# STM32F1_720.net
KiCad netlist of a schematic drawn in Altium Designer
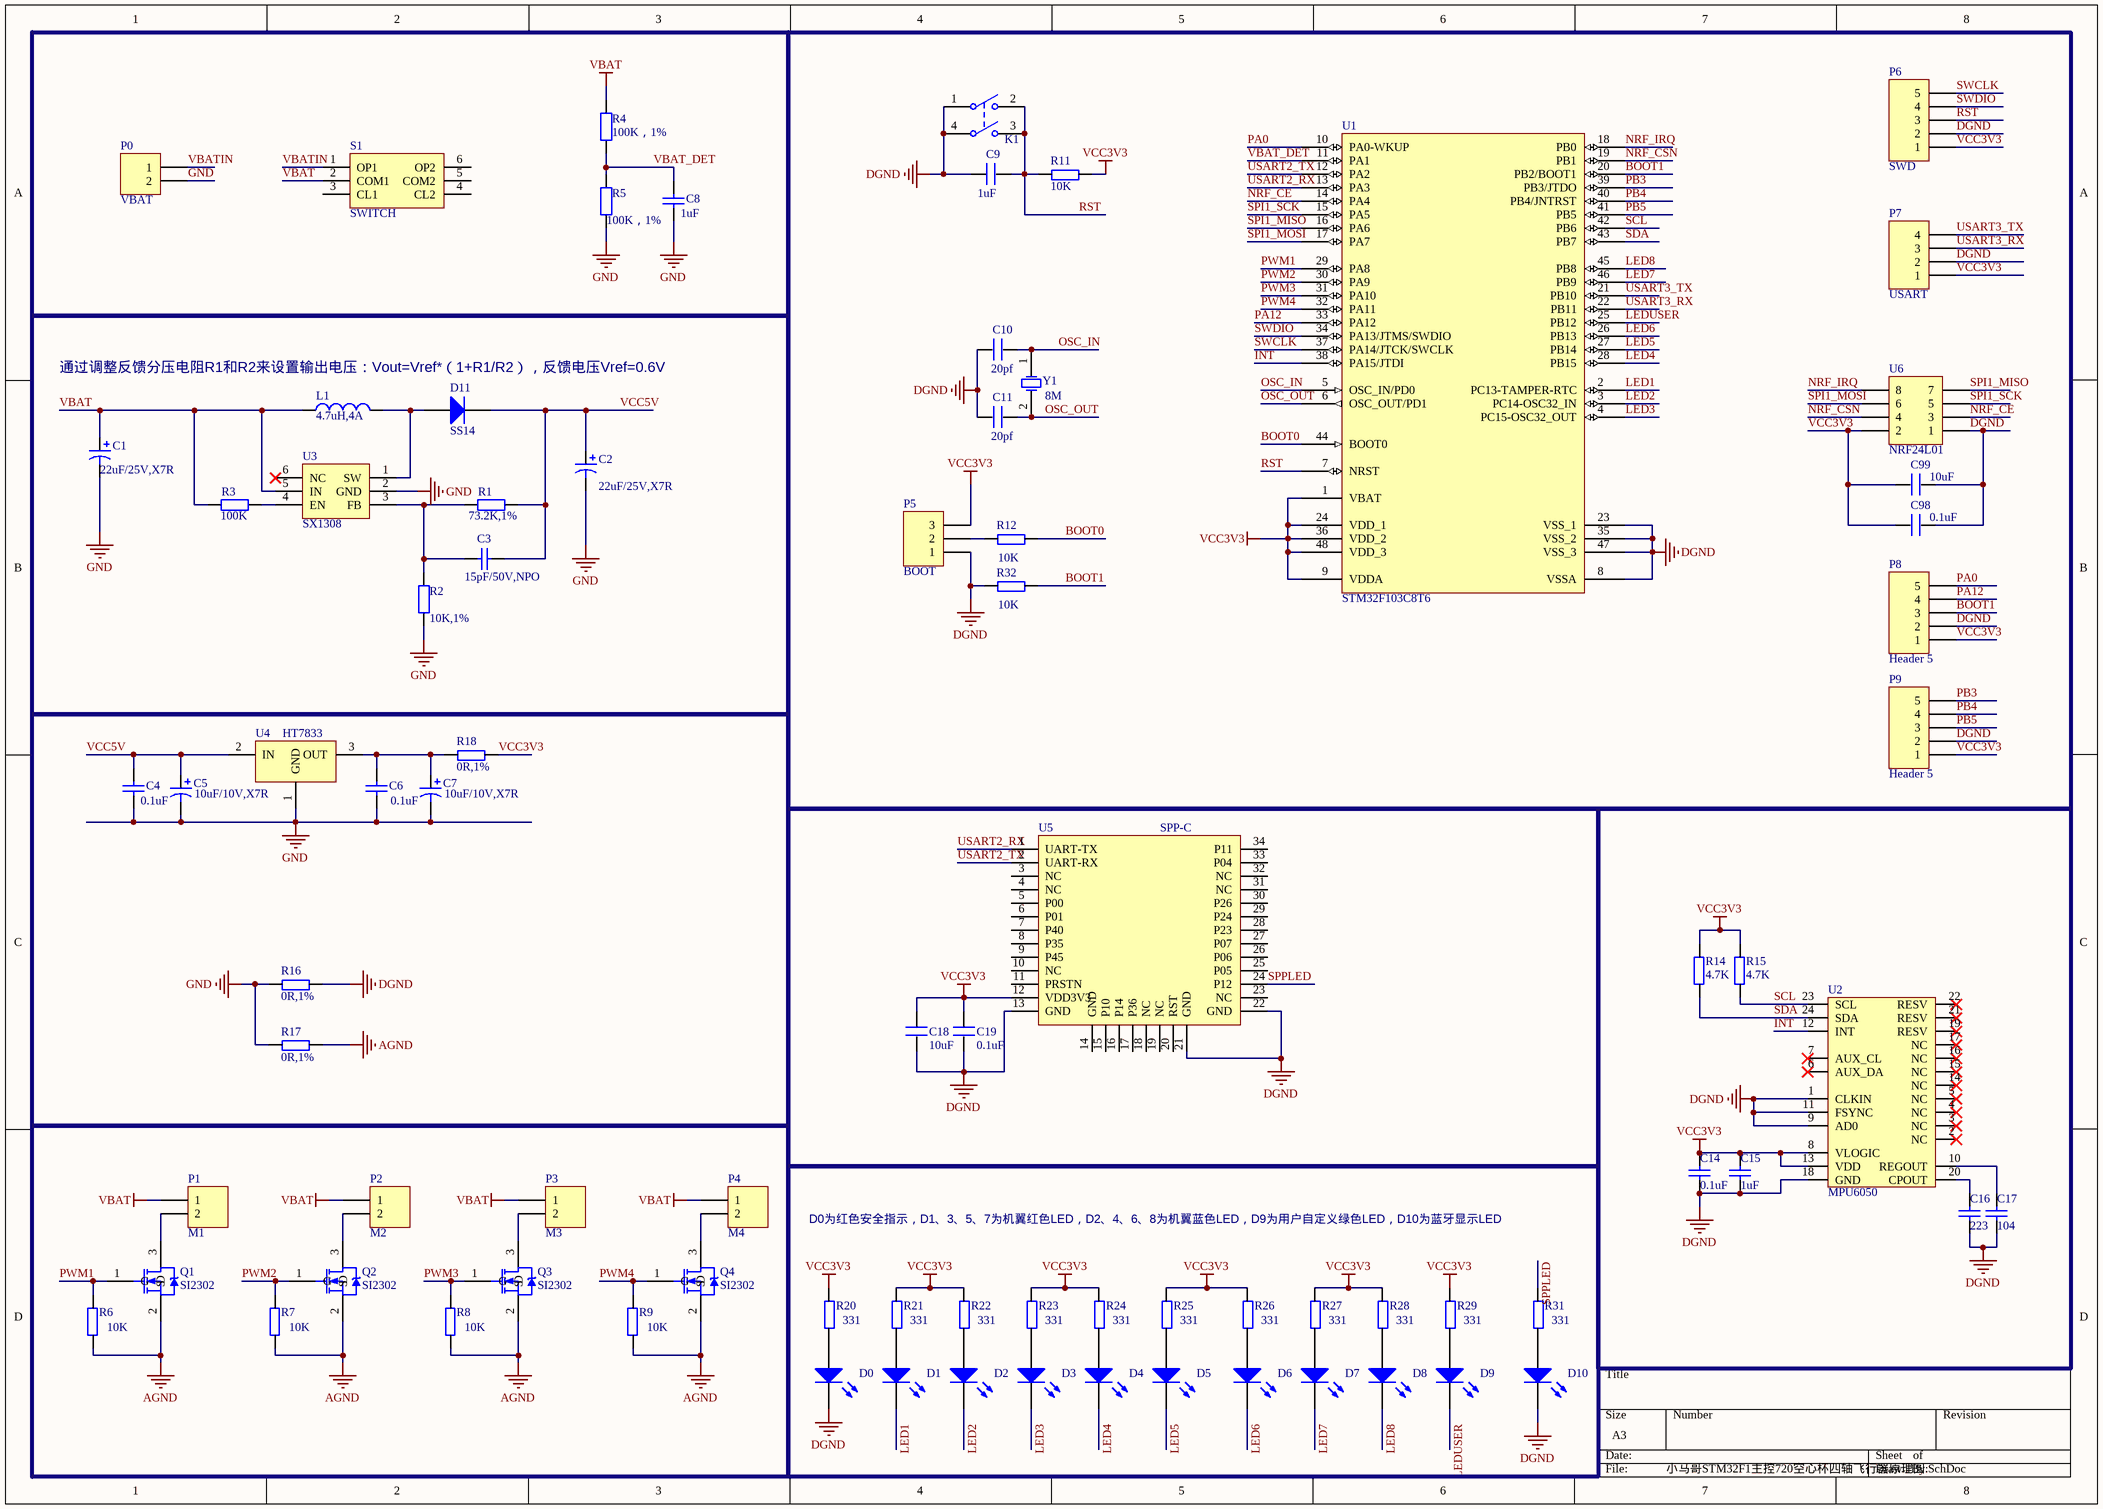
[diagram p0: 小马哥STM32F1主控720空心杯四轴飞行器原理图.SchDoc]

(export (version "E")
  (design (tool "Eeschema 10.0.6"))
  (components
    (comp (ref "C1")
      (value "22uF/25V,X7R")
      (footprint "LC-1206_C")
      (description "Polarized Capacitor (Radial)")
      (fields (field (name "Comment") "Cap Pol1") (field (name "PUBLISHER") "Altium Limited"))
      (libsource (lib "Miscellaneous Devices") (part "Cap Pol1"))
    )
    (comp (ref "C2")
      (value "22uF/25V,X7R")
      (footprint "LC-1206_C")
      (description "Polarized Capacitor (Radial)")
      (fields (field (name "Comment") "Cap Pol1") (field (name "PUBLISHER") "Altium Limited"))
      (libsource (lib "Miscellaneous Devices") (part "Cap Pol1"))
    )
    (comp (ref "C3")
      (value "15pF/50V,NPO")
      (footprint "LC-0603_C")
      (description "Capacitor")
      (fields (field (name "Comment") "Cap") (field (name "PUBLISHER") "Altium Limited"))
      (libsource (lib "Miscellaneous Devices") (part "Cap"))
    )
    (comp (ref "C4")
      (value "0.1uF")
      (footprint "LC-0603_C")
      (description "Capacitor")
      (fields (field (name "Comment") "Cap") (field (name "PUBLISHER") "Altium Limited"))
      (libsource (lib "Miscellaneous Devices") (part "Cap"))
    )
    (comp (ref "C5")
      (value "10uF/10V,X7R")
      (footprint "LC-1206_C")
      (description "Polarized Capacitor (Radial)")
      (fields (field (name "Comment") "Cap Pol1") (field (name "PUBLISHER") "Altium Limited"))
      (libsource (lib "Miscellaneous Devices") (part "Cap Pol1"))
    )
    (comp (ref "C6")
      (value "0.1uF")
      (footprint "LC-0603_C")
      (description "Capacitor")
      (fields (field (name "Comment") "Cap") (field (name "PUBLISHER") "Altium Limited"))
      (libsource (lib "Miscellaneous Devices") (part "Cap"))
    )
    (comp (ref "C7")
      (value "10uF/10V,X7R")
      (footprint "LC-1206_C")
      (description "Polarized Capacitor (Radial)")
      (fields (field (name "Comment") "Cap Pol1") (field (name "PUBLISHER") "Altium Limited"))
      (libsource (lib "Miscellaneous Devices") (part "Cap Pol1"))
    )
    (comp (ref "C8")
      (value "1uF")
      (footprint "LC-0603_C")
      (description "Capacitor")
      (fields (field (name "Comment") "Cap") (field (name "PUBLISHER") "Altium Limited"))
      (libsource (lib "Miscellaneous Devices") (part "Cap"))
    )
    (comp (ref "C9")
      (value "1uF")
      (footprint "LC-0603_C")
      (libsource (lib "Explorer STM32F407封装库") (part "C_1"))
    )
    (comp (ref "C10")
      (value "20pf")
      (footprint "LC-0603_C")
      (libsource (lib "Explorer STM32F407封装库") (part "C"))
    )
    (comp (ref "C11")
      (value "20pf")
      (footprint "LC-0603_C")
      (libsource (lib "Explorer STM32F407封装库") (part "C"))
    )
    (comp (ref "C14")
      (value "0.1uF")
      (footprint "LC-0603_C")
      (description "Capacitor")
      (fields (field (name "PUBLISHER") "Altium Limited"))
      (libsource (lib "Miscellaneous Devices") (part "Cap"))
    )
    (comp (ref "C15")
      (value "1uF")
      (footprint "LC-0603_C")
      (description "Capacitor")
      (fields (field (name "PUBLISHER") "Altium Limited"))
      (libsource (lib "Miscellaneous Devices") (part "Cap"))
    )
    (comp (ref "C16")
      (value "223")
      (footprint "LC-0603_C")
      (description "Capacitor")
      (fields (field (name "PUBLISHER") "Altium Limited"))
      (libsource (lib "Miscellaneous Devices") (part "Cap"))
    )
    (comp (ref "C17")
      (value "104")
      (footprint "LC-0603_C")
      (description "Capacitor")
      (fields (field (name "PUBLISHER") "Altium Limited"))
      (libsource (lib "Miscellaneous Devices") (part "Cap"))
    )
    (comp (ref "C18")
      (value "10uF")
      (footprint "LC-0805_C")
      (libsource (lib "Explorer STM32F407封装库") (part "C"))
    )
    (comp (ref "C19")
      (value "0.1uF")
      (footprint "LC-0603_C")
      (libsource (lib "Explorer STM32F407封装库") (part "C"))
    )
    (comp (ref "C98")
      (value "0.1uF")
      (footprint "LC-0603_C")
      (fields (field (name "Comment") "1uF"))
      (libsource (lib "Explorer STM32F407封装库") (part "C_1"))
    )
    (comp (ref "C99")
      (value "10uF")
      (footprint "LC-0805_C")
      (fields (field (name "Comment") "1uF"))
      (libsource (lib "Explorer STM32F407封装库") (part "C_1"))
    )
    (comp (ref "D0")
      (value "LED0")
      (footprint "LC-0805_LED_S1")
      (description "Typical INFRARED GaAs LED")
      (fields (field (name "PUBLISHER") "Altium Limited"))
      (libsource (lib "Miscellaneous Devices") (part "LED0"))
    )
    (comp (ref "D1")
      (value "LED0")
      (footprint "LC-0805_LED_S1")
      (description "Typical INFRARED GaAs LED")
      (fields (field (name "PUBLISHER") "Altium Limited"))
      (libsource (lib "Miscellaneous Devices") (part "LED0"))
    )
    (comp (ref "D2")
      (value "LED0")
      (footprint "LC-0805_LED_S1")
      (description "Typical INFRARED GaAs LED")
      (fields (field (name "PUBLISHER") "Altium Limited"))
      (libsource (lib "Miscellaneous Devices") (part "LED0"))
    )
    (comp (ref "D3")
      (value "LED0")
      (footprint "LC-0805_LED_S1")
      (description "Typical INFRARED GaAs LED")
      (fields (field (name "PUBLISHER") "Altium Limited"))
      (libsource (lib "Miscellaneous Devices") (part "LED0"))
    )
    (comp (ref "D4")
      (value "LED0")
      (footprint "LC-0805_LED_S1")
      (description "Typical INFRARED GaAs LED")
      (fields (field (name "PUBLISHER") "Altium Limited"))
      (libsource (lib "Miscellaneous Devices") (part "LED0"))
    )
    (comp (ref "D5")
      (value "LED0")
      (footprint "LC-0805_LED_S1")
      (description "Typical INFRARED GaAs LED")
      (fields (field (name "PUBLISHER") "Altium Limited"))
      (libsource (lib "Miscellaneous Devices") (part "LED0"))
    )
    (comp (ref "D6")
      (value "LED0")
      (footprint "LC-0805_LED_S1")
      (description "Typical INFRARED GaAs LED")
      (fields (field (name "PUBLISHER") "Altium Limited"))
      (libsource (lib "Miscellaneous Devices") (part "LED0"))
    )
    (comp (ref "D7")
      (value "LED0")
      (footprint "LC-0805_LED_S1")
      (description "Typical INFRARED GaAs LED")
      (fields (field (name "PUBLISHER") "Altium Limited"))
      (libsource (lib "Miscellaneous Devices") (part "LED0"))
    )
    (comp (ref "D8")
      (value "LED0")
      (footprint "LC-0805_LED_S1")
      (description "Typical INFRARED GaAs LED")
      (fields (field (name "PUBLISHER") "Altium Limited"))
      (libsource (lib "Miscellaneous Devices") (part "LED0"))
    )
    (comp (ref "D9")
      (value "LED0")
      (footprint "LC-0805_LED_S1")
      (description "Typical INFRARED GaAs LED")
      (fields (field (name "PUBLISHER") "Altium Limited"))
      (libsource (lib "Miscellaneous Devices") (part "LED0"))
    )
    (comp (ref "D10")
      (value "LED0")
      (footprint "LC-0805_LED_S1")
      (description "Typical INFRARED GaAs LED")
      (fields (field (name "PUBLISHER") "Altium Limited"))
      (libsource (lib "Miscellaneous Devices") (part "LED0"))
    )
    (comp (ref "D11")
      (value "SS14")
      (footprint "LC-DO-214AC")
      (description "1 Amp General Purpose Rectifier")
      (fields (field (name "PUBLISHER") "Altium Limited"))
      (libsource (lib "Miscellaneous Devices") (part "Diode 1N4001"))
    )
    (comp (ref "K1")
      (value "SW-DPST")
      (footprint "SWITCH2")
      (description "Double-Pole, Single-Throw Switch")
      (fields (field (name "PUBLISHER") "Altium Limited"))
      (libsource (lib "Miscellaneous Devices") (part "SW-DPST"))
    )
    (comp (ref "L1")
      (value "4.7uH,4A")
      (footprint "LC-1812_L")
      (description "Inductor")
      (fields (field (name "PUBLISHER") "Altium Limited"))
      (libsource (lib "Miscellaneous Devices") (part "Inductor"))
    )
    (comp (ref "P0")
      (value "VBAT")
      (footprint "HDR1X2")
      (description "Header, 2-Pin")
      (fields (field (name "PUBLISHER") "Altium Limited"))
      (libsource (lib "") (part "Header 2_1"))
    )
    (comp (ref "P1")
      (value "M1")
      (footprint "HDR1X2")
      (description "Header, 2-Pin")
      (fields (field (name "PUBLISHER") "Altium Limited"))
      (libsource (lib "Miscellaneous Connectors") (part "Header 2"))
    )
    (comp (ref "P2")
      (value "M2")
      (footprint "HDR1X2")
      (description "Header, 2-Pin")
      (fields (field (name "PUBLISHER") "Altium Limited"))
      (libsource (lib "Miscellaneous Connectors") (part "Header 2"))
    )
    (comp (ref "P3")
      (value "M3")
      (footprint "HDR1X2")
      (description "Header, 2-Pin")
      (fields (field (name "PUBLISHER") "Altium Limited"))
      (libsource (lib "Miscellaneous Connectors") (part "Header 2"))
    )
    (comp (ref "P4")
      (value "M4")
      (footprint "HDR1X2")
      (description "Header, 2-Pin")
      (fields (field (name "PUBLISHER") "Altium Limited"))
      (libsource (lib "Miscellaneous Connectors") (part "Header 2"))
    )
    (comp (ref "P5")
      (value "BOOT")
      (footprint "HDR1X3")
      (description "Header, 3-Pin")
      (fields (field (name "PUBLISHER") "Altium Limited"))
      (libsource (lib "Miscellaneous Connectors") (part "Header 3"))
    )
    (comp (ref "P6")
      (value "SWD")
      (footprint "HDR1X5")
      (description "Header, 5-Pin")
      (fields (field (name "PUBLISHER") "Altium Limited"))
      (libsource (lib "Miscellaneous Connectors") (part "Header 5"))
    )
    (comp (ref "P7")
      (value "USART")
      (footprint "HDR1X4")
      (description "Header, 4-Pin")
      (fields (field (name "PUBLISHER") "Altium Limited"))
      (libsource (lib "Miscellaneous Connectors") (part "Header 4"))
    )
    (comp (ref "P8")
      (value "Header 5")
      (footprint "HDR1X5")
      (description "Header, 5-Pin")
      (fields (field (name "PUBLISHER") "Altium Limited"))
      (libsource (lib "Miscellaneous Connectors") (part "Header 5"))
    )
    (comp (ref "P9")
      (value "Header 5")
      (footprint "HDR1X5")
      (description "Header, 5-Pin")
      (fields (field (name "PUBLISHER") "Altium Limited"))
      (libsource (lib "Miscellaneous Connectors") (part "Header 5"))
    )
    (comp (ref "Q1")
      (value "SI2302")
      (footprint "LC-SOT-23(SOT-23-3)")
      (description "N-Channel Power MOSFET")
      (fields (field (name "PUBLISHER") "Altium Limited"))
      (libsource (lib "Miscellaneous Devices") (part "NMOS-2"))
    )
    (comp (ref "Q2")
      (value "SI2302")
      (footprint "LC-SOT-23(SOT-23-3)")
      (description "N-Channel Power MOSFET")
      (fields (field (name "PUBLISHER") "Altium Limited"))
      (libsource (lib "Miscellaneous Devices") (part "NMOS-2"))
    )
    (comp (ref "Q3")
      (value "SI2302")
      (footprint "LC-SOT-23(SOT-23-3)")
      (description "N-Channel Power MOSFET")
      (fields (field (name "PUBLISHER") "Altium Limited"))
      (libsource (lib "Miscellaneous Devices") (part "NMOS-2"))
    )
    (comp (ref "Q4")
      (value "SI2302")
      (footprint "LC-SOT-23(SOT-23-3)")
      (description "N-Channel Power MOSFET")
      (fields (field (name "PUBLISHER") "Altium Limited"))
      (libsource (lib "Miscellaneous Devices") (part "NMOS-2"))
    )
    (comp (ref "R1")
      (value "73.2K,1%")
      (footprint "LC-0603_R")
      (description "Resistor")
      (fields (field (name "Comment") "Res2") (field (name "PUBLISHER") "Altium Limited"))
      (libsource (lib "Miscellaneous Devices") (part "Res2"))
    )
    (comp (ref "R2")
      (value "10K,1%")
      (footprint "LC-0603_R")
      (description "Resistor")
      (fields (field (name "Comment") "Res2") (field (name "PUBLISHER") "Altium Limited"))
      (libsource (lib "") (part "Res2_1"))
    )
    (comp (ref "R3")
      (value "100K")
      (footprint "LC-0603_R")
      (description "Resistor")
      (fields (field (name "Comment") "Res2") (field (name "PUBLISHER") "Altium Limited"))
      (libsource (lib "Miscellaneous Devices") (part "Res2"))
    )
    (comp (ref "R4")
      (value "100K，1%")
      (footprint "LC-0603_R")
      (description "Resistor")
      (fields (field (name "Comment") "Res2") (field (name "PUBLISHER") "Altium Limited"))
      (libsource (lib "") (part "Res2_1"))
    )
    (comp (ref "R5")
      (value "100K，1%")
      (footprint "LC-0603_R")
      (description "Resistor")
      (fields (field (name "Comment") "Res2") (field (name "PUBLISHER") "Altium Limited"))
      (libsource (lib "") (part "Res2_1"))
    )
    (comp (ref "R6")
      (value "10K")
      (footprint "LC-0603_R")
      (libsource (lib "Explorer STM32F407封装库") (part "R"))
    )
    (comp (ref "R7")
      (value "10K")
      (footprint "LC-0603_R")
      (libsource (lib "Explorer STM32F407封装库") (part "R"))
    )
    (comp (ref "R8")
      (value "10K")
      (footprint "LC-0603_R")
      (libsource (lib "Explorer STM32F407封装库") (part "R"))
    )
    (comp (ref "R9")
      (value "10K")
      (footprint "LC-0603_R")
      (libsource (lib "Explorer STM32F407封装库") (part "R"))
    )
    (comp (ref "R11")
      (value "10K")
      (footprint "LC-0603_R")
      (libsource (lib "Explorer STM32F407封装库") (part "R_1"))
    )
    (comp (ref "R12")
      (value "10K")
      (footprint "LC-0603_R")
      (libsource (lib "Explorer STM32F407封装库") (part "R"))
    )
    (comp (ref "R14")
      (value "4.7K")
      (footprint "LC-0603_R")
      (libsource (lib "Explorer STM32F407封装库") (part "R_1"))
    )
    (comp (ref "R15")
      (value "4.7K")
      (footprint "LC-0603_R")
      (libsource (lib "Explorer STM32F407封装库") (part "R_1"))
    )
    (comp (ref "R16")
      (value "0R,1%")
      (footprint "LC-0805_R")
      (libsource (lib "Explorer STM32F407封装库") (part "R"))
    )
    (comp (ref "R17")
      (value "0R,1%")
      (footprint "LC-0805_R")
      (libsource (lib "Explorer STM32F407封装库") (part "R"))
    )
    (comp (ref "R18")
      (value "0R,1%")
      (footprint "LC-0805_R")
      (libsource (lib "Explorer STM32F407封装库") (part "R"))
    )
    (comp (ref "R20")
      (value "331")
      (footprint "LC-0603_R")
      (libsource (lib "Explorer STM32F407封装库") (part "R_1"))
    )
    (comp (ref "R21")
      (value "331")
      (footprint "LC-0603_R")
      (libsource (lib "Explorer STM32F407封装库") (part "R_1"))
    )
    (comp (ref "R22")
      (value "331")
      (footprint "LC-0603_R")
      (libsource (lib "Explorer STM32F407封装库") (part "R_1"))
    )
    (comp (ref "R23")
      (value "331")
      (footprint "LC-0603_R")
      (libsource (lib "Explorer STM32F407封装库") (part "R_1"))
    )
    (comp (ref "R24")
      (value "331")
      (footprint "LC-0603_R")
      (libsource (lib "Explorer STM32F407封装库") (part "R_1"))
    )
    (comp (ref "R25")
      (value "331")
      (footprint "LC-0603_R")
      (libsource (lib "Explorer STM32F407封装库") (part "R_1"))
    )
    (comp (ref "R26")
      (value "331")
      (footprint "LC-0603_R")
      (libsource (lib "Explorer STM32F407封装库") (part "R_1"))
    )
    (comp (ref "R27")
      (value "331")
      (footprint "LC-0603_R")
      (libsource (lib "Explorer STM32F407封装库") (part "R_1"))
    )
    (comp (ref "R28")
      (value "331")
      (footprint "LC-0603_R")
      (libsource (lib "Explorer STM32F407封装库") (part "R_1"))
    )
    (comp (ref "R29")
      (value "331")
      (footprint "LC-0603_R")
      (libsource (lib "Explorer STM32F407封装库") (part "R_1"))
    )
    (comp (ref "R31")
      (value "331")
      (footprint "LC-0603_R")
      (libsource (lib "Explorer STM32F407封装库") (part "R_1"))
    )
    (comp (ref "R32")
      (value "10K")
      (footprint "LC-0603_R")
      (libsource (lib "Explorer STM32F407封装库") (part "R"))
    )
    (comp (ref "S1") (value "SWITCH") (footprint "SWITCH_6") (libsource (lib "mzwlib") (part "SWITCH")))
    (comp (ref "U1")
      (value "STM32F103C8T6")
      (footprint "LC-LQFP-48_7x7x05P")
      (description "STM32 ARM-based 32-bit MCU with 64 Kbytes Flash, 48-pin LQFP, Industrial Temperature")
      (fields (field (name "PUBLISHER") "Altium Limited"))
      (libsource (lib "ST Microcontroller 32-Bit STM32") (part "STM32F103C8T6"))
    )
    (comp (ref "U2")
      (value "MPU6050")
      (footprint "LC-QFN-24_4x4x05P")
      (description "9轴运动处理传感器")
      (libsource (lib "Explorer STM32F407封装库") (part "MPU6050"))
    )
    (comp (ref "U3") (value "SX1308") (footprint "LC-SOT-23-6") (libsource (lib "mzwlib") (part "SX1308")))
    (comp (ref "U4")
      (value "HT7833")
      (footprint "LC-SOT-89(SOT-89-3)")
      (libsource (lib "mzwlib") (part "HT7833"))
    )
    (comp (ref "U5") (value "SPP-C") (footprint "SPP-C") (libsource (lib "mzwlib") (part "SPP-C")))
    (comp (ref "U6")
      (value "NRF24L01")
      (footprint "LC-HDR2X4H")
      (description "Header, 4-Pin, Dual row, Right Angle")
      (fields (field (name "PUBLISHER") "Altium Limited"))
      (libsource (lib "Miscellaneous Connectors") (part "Header 4X2H"))
    )
    (comp (ref "Y1")
      (value "~")
      (footprint "LC-HC-49S")
      (description "Crystal Oscillator")
      (fields (field (name "ALTIUM_UNNAMED_1") "8M") (field (name "PUBLISHER") "Altium Limited"))
      (libsource (lib "Explorer STM32F407封装库") (part "XTAL"))
    )
  )
  (nets
    (net (code "1") (name "/BOOT0") (class "Default")
      (node (ref "R12") (pin "2") (pintype "passive"))
      (node (ref "U1") (pin "44") (pinfunction "BOOT0_44") (pintype "input"))
    )
    (net (code "2") (name "/BOOT1") (class "Default")
      (node (ref "P8") (pin "3") (pinfunction "3_3") (pintype "passive"))
      (node (ref "R32") (pin "2") (pintype "passive"))
      (node (ref "U1") (pin "20") (pinfunction "PB2/BOOT1_20") (pintype "bidirectional"))
    )
    (net (code "3") (name "/INT") (class "Default")
      (node (ref "U1") (pin "38") (pinfunction "PA15/JTDI_38") (pintype "bidirectional"))
      (node (ref "U2") (pin "12") (pinfunction "INT_12") (pintype "passive"))
    )
    (net (code "4") (name "/LED1") (class "Default")
      (node (ref "D1") (pin "2") (pinfunction "K_2") (pintype "passive"))
      (node (ref "U1") (pin "2") (pinfunction "PC13-TAMPER-RTC_2") (pintype "bidirectional"))
    )
    (net (code "5") (name "/LED2") (class "Default")
      (node (ref "D2") (pin "2") (pinfunction "K_2") (pintype "passive"))
      (node (ref "U1") (pin "3") (pinfunction "PC14-OSC32_IN_3") (pintype "bidirectional"))
    )
    (net (code "6") (name "/LED3") (class "Default")
      (node (ref "D3") (pin "2") (pinfunction "K_2") (pintype "passive"))
      (node (ref "U1") (pin "4") (pinfunction "PC15-OSC32_OUT_4") (pintype "bidirectional"))
    )
    (net (code "7") (name "/LED4") (class "Default")
      (node (ref "D4") (pin "2") (pinfunction "K_2") (pintype "passive"))
      (node (ref "U1") (pin "28") (pinfunction "PB15_28") (pintype "bidirectional"))
    )
    (net (code "8") (name "/LED5") (class "Default")
      (node (ref "D5") (pin "2") (pinfunction "K_2") (pintype "passive"))
      (node (ref "U1") (pin "27") (pinfunction "PB14_27") (pintype "bidirectional"))
    )
    (net (code "9") (name "/LED6") (class "Default")
      (node (ref "D6") (pin "2") (pinfunction "K_2") (pintype "passive"))
      (node (ref "U1") (pin "26") (pinfunction "PB13_26") (pintype "bidirectional"))
    )
    (net (code "10") (name "/LED7") (class "Default")
      (node (ref "D7") (pin "2") (pinfunction "K_2") (pintype "passive"))
      (node (ref "U1") (pin "46") (pinfunction "PB9_46") (pintype "bidirectional"))
    )
    (net (code "11") (name "/LED8") (class "Default")
      (node (ref "D8") (pin "2") (pinfunction "K_2") (pintype "passive"))
      (node (ref "U1") (pin "45") (pinfunction "PB8_45") (pintype "bidirectional"))
    )
    (net (code "12") (name "/LEDUSER") (class "Default")
      (node (ref "D9") (pin "2") (pinfunction "K_2") (pintype "passive"))
      (node (ref "U1") (pin "25") (pinfunction "PB12_25") (pintype "bidirectional"))
    )
    (net (code "13") (name "/NRF_CE") (class "Default")
      (node (ref "U1") (pin "14") (pinfunction "PA4_14") (pintype "bidirectional"))
      (node (ref "U6") (pin "3") (pinfunction "3_3") (pintype "passive"))
    )
    (net (code "14") (name "/NRF_CSN") (class "Default")
      (node (ref "U1") (pin "19") (pinfunction "PB1_19") (pintype "bidirectional"))
      (node (ref "U6") (pin "4") (pinfunction "4_4") (pintype "passive"))
    )
    (net (code "15") (name "/NRF_IRQ") (class "Default")
      (node (ref "U1") (pin "18") (pinfunction "PB0_18") (pintype "bidirectional"))
      (node (ref "U6") (pin "8") (pinfunction "8_8") (pintype "passive"))
    )
    (net (code "16") (name "/OSC_IN") (class "Default")
      (node (ref "C10") (pin "2") (pintype "passive"))
      (node (ref "U1") (pin "5") (pinfunction "OSC_IN/PD0_5") (pintype "input"))
      (node (ref "Y1") (pin "1") (pinfunction "OSC1_1") (pintype "passive"))
    )
    (net (code "17") (name "/OSC_OUT") (class "Default")
      (node (ref "C11") (pin "2") (pintype "passive"))
      (node (ref "U1") (pin "6") (pinfunction "OSC_OUT/PD1_6") (pintype "output"))
      (node (ref "Y1") (pin "2") (pinfunction "OSC2_2") (pintype "passive"))
    )
    (net (code "18") (name "/PA0") (class "Default")
      (node (ref "P8") (pin "5") (pinfunction "5_5") (pintype "passive"))
      (node (ref "U1") (pin "10") (pinfunction "PA0-WKUP_10") (pintype "bidirectional"))
    )
    (net (code "19") (name "/PA12") (class "Default")
      (node (ref "P8") (pin "4") (pinfunction "4_4") (pintype "passive"))
      (node (ref "U1") (pin "33") (pinfunction "PA12_33") (pintype "bidirectional"))
    )
    (net (code "20") (name "/PB3") (class "Default")
      (node (ref "P9") (pin "5") (pinfunction "5_5") (pintype "passive"))
      (node (ref "U1") (pin "39") (pinfunction "PB3/JTDO_39") (pintype "bidirectional"))
    )
    (net (code "21") (name "/PB4") (class "Default")
      (node (ref "P9") (pin "4") (pinfunction "4_4") (pintype "passive"))
      (node (ref "U1") (pin "40") (pinfunction "PB4/JNTRST_40") (pintype "bidirectional"))
    )
    (net (code "22") (name "/PB5") (class "Default")
      (node (ref "P9") (pin "3") (pinfunction "3_3") (pintype "passive"))
      (node (ref "U1") (pin "41") (pinfunction "PB5_41") (pintype "bidirectional"))
    )
    (net (code "23") (name "/PWM1") (class "Default")
      (node (ref "Q1") (pin "1") (pinfunction "G_1") (pintype "passive"))
      (node (ref "R6") (pin "1") (pintype "passive"))
      (node (ref "U1") (pin "29") (pinfunction "PA8_29") (pintype "bidirectional"))
    )
    (net (code "24") (name "/PWM2") (class "Default")
      (node (ref "Q2") (pin "1") (pinfunction "G_1") (pintype "passive"))
      (node (ref "R7") (pin "1") (pintype "passive"))
      (node (ref "U1") (pin "30") (pinfunction "PA9_30") (pintype "bidirectional"))
    )
    (net (code "25") (name "/PWM3") (class "Default")
      (node (ref "Q3") (pin "1") (pinfunction "G_1") (pintype "passive"))
      (node (ref "R8") (pin "1") (pintype "passive"))
      (node (ref "U1") (pin "31") (pinfunction "PA10_31") (pintype "bidirectional"))
    )
    (net (code "26") (name "/PWM4") (class "Default")
      (node (ref "Q4") (pin "1") (pinfunction "G_1") (pintype "passive"))
      (node (ref "R9") (pin "1") (pintype "passive"))
      (node (ref "U1") (pin "32") (pinfunction "PA11_32") (pintype "bidirectional"))
    )
    (net (code "27") (name "/RST") (class "Default")
      (node (ref "C9") (pin "2") (pintype "passive"))
      (node (ref "K1") (pin "2") (pinfunction "NO1_2") (pintype "passive"))
      (node (ref "K1") (pin "3") (pinfunction "NO2_3") (pintype "passive"))
      (node (ref "P6") (pin "3") (pinfunction "3_3") (pintype "passive"))
      (node (ref "R11") (pin "1") (pintype "passive"))
      (node (ref "U1") (pin "7") (pinfunction "NRST_7") (pintype "bidirectional"))
    )
    (net (code "28") (name "/SCL") (class "Default")
      (node (ref "R15") (pin "2") (pintype "passive"))
      (node (ref "U1") (pin "42") (pinfunction "PB6_42") (pintype "bidirectional"))
      (node (ref "U2") (pin "23") (pinfunction "SCL_23") (pintype "passive"))
    )
    (net (code "29") (name "/SDA") (class "Default")
      (node (ref "R14") (pin "2") (pintype "passive"))
      (node (ref "U1") (pin "43") (pinfunction "PB7_43") (pintype "bidirectional"))
      (node (ref "U2") (pin "24") (pinfunction "SDA_24") (pintype "passive"))
    )
    (net (code "30") (name "/SPI1_MISO") (class "Default")
      (node (ref "U1") (pin "16") (pinfunction "PA6_16") (pintype "bidirectional"))
      (node (ref "U6") (pin "7") (pinfunction "7_7") (pintype "passive"))
    )
    (net (code "31") (name "/SPI1_MOSI") (class "Default")
      (node (ref "U1") (pin "17") (pinfunction "PA7_17") (pintype "bidirectional"))
      (node (ref "U6") (pin "6") (pinfunction "6_6") (pintype "passive"))
    )
    (net (code "32") (name "/SPI1_SCK") (class "Default")
      (node (ref "U1") (pin "15") (pinfunction "PA5_15") (pintype "bidirectional"))
      (node (ref "U6") (pin "5") (pinfunction "5_5") (pintype "passive"))
    )
    (net (code "33") (name "/SPPLED") (class "Default")
      (node (ref "R31") (pin "2") (pintype "passive"))
      (node (ref "U5") (pin "24") (pinfunction "P12_24") (pintype "passive"))
    )
    (net (code "34") (name "/SWCLK") (class "Default")
      (node (ref "P6") (pin "5") (pinfunction "5_5") (pintype "passive"))
      (node (ref "U1") (pin "37") (pinfunction "PA14/JTCK/SWCLK_37") (pintype "bidirectional"))
    )
    (net (code "35") (name "/SWDIO") (class "Default")
      (node (ref "P6") (pin "4") (pinfunction "4_4") (pintype "passive"))
      (node (ref "U1") (pin "34") (pinfunction "PA13/JTMS/SWDIO_34") (pintype "bidirectional"))
    )
    (net (code "36") (name "/USART2_RX") (class "Default")
      (node (ref "U1") (pin "13") (pinfunction "PA3_13") (pintype "bidirectional"))
      (node (ref "U5") (pin "1") (pinfunction "UART-TX_1") (pintype "passive"))
    )
    (net (code "37") (name "/USART2_TX") (class "Default")
      (node (ref "U1") (pin "12") (pinfunction "PA2_12") (pintype "bidirectional"))
      (node (ref "U5") (pin "2") (pinfunction "UART-RX_2") (pintype "passive"))
    )
    (net (code "38") (name "/USART3_RX") (class "Default")
      (node (ref "P7") (pin "3") (pinfunction "3_3") (pintype "passive"))
      (node (ref "U1") (pin "22") (pinfunction "PB11_22") (pintype "bidirectional"))
    )
    (net (code "39") (name "/USART3_TX") (class "Default")
      (node (ref "P7") (pin "4") (pinfunction "4_4") (pintype "passive"))
      (node (ref "U1") (pin "21") (pinfunction "PB10_21") (pintype "bidirectional"))
    )
    (net (code "40") (name "/VBATIN") (class "Default")
      (node (ref "P0") (pin "1") (pinfunction "1_1") (pintype "passive"))
      (node (ref "S1") (pin "1") (pinfunction "OP1_1") (pintype "passive"))
    )
    (net (code "41") (name "/VBAT_DET") (class "Default")
      (node (ref "C8") (pin "2") (pinfunction "2_2") (pintype "passive"))
      (node (ref "R4") (pin "1") (pinfunction "1_1") (pintype "passive"))
      (node (ref "R5") (pin "2") (pinfunction "2_2") (pintype "passive"))
      (node (ref "U1") (pin "11") (pinfunction "PA1_11") (pintype "bidirectional"))
    )
    (net (code "42") (name "/VCC5V") (class "Default")
      (node (ref "C2") (pin "1") (pinfunction "1_1") (pintype "passive"))
      (node (ref "C3") (pin "2") (pinfunction "2_2") (pintype "passive"))
      (node (ref "C4") (pin "2") (pinfunction "2_2") (pintype "passive"))
      (node (ref "C5") (pin "1") (pinfunction "1_1") (pintype "passive"))
      (node (ref "D11") (pin "2") (pinfunction "K_2") (pintype "passive"))
      (node (ref "R1") (pin "2") (pinfunction "2_2") (pintype "passive"))
      (node (ref "U4") (pin "2") (pinfunction "IN_2") (pintype "passive"))
    )
    (net (code "43") (name "AGND") (class "Default")
      (node (ref "Q1") (pin "2") (pinfunction "S_2") (pintype "passive"))
      (node (ref "Q2") (pin "2") (pinfunction "S_2") (pintype "passive"))
      (node (ref "Q3") (pin "2") (pinfunction "S_2") (pintype "passive"))
      (node (ref "Q4") (pin "2") (pinfunction "S_2") (pintype "passive"))
      (node (ref "R17") (pin "2") (pintype "passive"))
      (node (ref "R6") (pin "2") (pintype "passive"))
      (node (ref "R7") (pin "2") (pintype "passive"))
      (node (ref "R8") (pin "2") (pintype "passive"))
      (node (ref "R9") (pin "2") (pintype "passive"))
    )
    (net (code "44") (name "DGND") (class "Default")
      (node (ref "C10") (pin "1") (pintype "passive"))
      (node (ref "C11") (pin "1") (pintype "passive"))
      (node (ref "C14") (pin "1") (pinfunction "1_1") (pintype "passive"))
      (node (ref "C15") (pin "1") (pinfunction "1_1") (pintype "passive"))
      (node (ref "C16") (pin "1") (pinfunction "1_1") (pintype "passive"))
      (node (ref "C17") (pin "1") (pinfunction "1_1") (pintype "passive"))
      (node (ref "C18") (pin "1") (pintype "passive"))
      (node (ref "C19") (pin "1") (pintype "passive"))
      (node (ref "C9") (pin "1") (pintype "passive"))
      (node (ref "C98") (pin "2") (pintype "passive"))
      (node (ref "C99") (pin "2") (pintype "passive"))
      (node (ref "D0") (pin "2") (pinfunction "K_2") (pintype "passive"))
      (node (ref "D10") (pin "2") (pinfunction "K_2") (pintype "passive"))
      (node (ref "K1") (pin "1") (pinfunction "COMMON1_1") (pintype "passive"))
      (node (ref "K1") (pin "4") (pinfunction "COMMON2_4") (pintype "passive"))
      (node (ref "P5") (pin "1") (pinfunction "1_1") (pintype "passive"))
      (node (ref "P6") (pin "2") (pinfunction "2_2") (pintype "passive"))
      (node (ref "P7") (pin "2") (pinfunction "2_2") (pintype "passive"))
      (node (ref "P8") (pin "2") (pinfunction "2_2") (pintype "passive"))
      (node (ref "P9") (pin "2") (pinfunction "2_2") (pintype "passive"))
      (node (ref "R16") (pin "2") (pintype "passive"))
      (node (ref "R32") (pin "1") (pintype "passive"))
      (node (ref "U1") (pin "23") (pinfunction "VSS_1_23") (pintype "power_in"))
      (node (ref "U1") (pin "35") (pinfunction "VSS_2_35") (pintype "power_in"))
      (node (ref "U1") (pin "47") (pinfunction "VSS_3_47") (pintype "power_in"))
      (node (ref "U1") (pin "8") (pinfunction "VSSA_8") (pintype "power_in"))
      (node (ref "U2") (pin "1") (pinfunction "CLKIN_1") (pintype "passive"))
      (node (ref "U2") (pin "11") (pinfunction "FSYNC_11") (pintype "passive"))
      (node (ref "U2") (pin "18") (pinfunction "GND_18") (pintype "passive"))
      (node (ref "U2") (pin "9") (pinfunction "AD0_9") (pintype "passive"))
      (node (ref "U5") (pin "13") (pinfunction "GND_13") (pintype "passive"))
      (node (ref "U5") (pin "21") (pinfunction "GND_21") (pintype "passive"))
      (node (ref "U5") (pin "22") (pinfunction "GND_22") (pintype "passive"))
      (node (ref "U6") (pin "1") (pinfunction "1_1") (pintype "passive"))
    )
    (net (code "45") (name "GND") (class "Default")
      (node (ref "C1") (pin "2") (pinfunction "2_2") (pintype "passive"))
      (node (ref "C2") (pin "2") (pinfunction "2_2") (pintype "passive"))
      (node (ref "C4") (pin "1") (pinfunction "1_1") (pintype "passive"))
      (node (ref "C5") (pin "2") (pinfunction "2_2") (pintype "passive"))
      (node (ref "C6") (pin "1") (pinfunction "1_1") (pintype "passive"))
      (node (ref "C7") (pin "2") (pinfunction "2_2") (pintype "passive"))
      (node (ref "C8") (pin "1") (pinfunction "1_1") (pintype "passive"))
      (node (ref "P0") (pin "2") (pinfunction "2_2") (pintype "passive"))
      (node (ref "R16") (pin "1") (pintype "passive"))
      (node (ref "R17") (pin "1") (pintype "passive"))
      (node (ref "R2") (pin "1") (pinfunction "1_1") (pintype "passive"))
      (node (ref "R5") (pin "1") (pinfunction "1_1") (pintype "passive"))
      (node (ref "U3") (pin "2") (pinfunction "GND_2") (pintype "passive"))
      (node (ref "U4") (pin "1") (pinfunction "GND_1") (pintype "passive"))
    )
    (net (code "46") (name "Net-(D0-A)") (class "Default")
      (node (ref "D0") (pin "1") (pinfunction "A_1") (pintype "passive"))
      (node (ref "R20") (pin "1") (pintype "passive"))
    )
    (net (code "47") (name "Net-(D1-A)") (class "Default")
      (node (ref "D1") (pin "1") (pinfunction "A_1") (pintype "passive"))
      (node (ref "R21") (pin "1") (pintype "passive"))
    )
    (net (code "48") (name "Net-(D2-A)") (class "Default")
      (node (ref "D2") (pin "1") (pinfunction "A_1") (pintype "passive"))
      (node (ref "R22") (pin "1") (pintype "passive"))
    )
    (net (code "49") (name "Net-(D3-A)") (class "Default")
      (node (ref "D3") (pin "1") (pinfunction "A_1") (pintype "passive"))
      (node (ref "R23") (pin "1") (pintype "passive"))
    )
    (net (code "50") (name "Net-(D4-A)") (class "Default")
      (node (ref "D4") (pin "1") (pinfunction "A_1") (pintype "passive"))
      (node (ref "R24") (pin "1") (pintype "passive"))
    )
    (net (code "51") (name "Net-(D5-A)") (class "Default")
      (node (ref "D5") (pin "1") (pinfunction "A_1") (pintype "passive"))
      (node (ref "R25") (pin "1") (pintype "passive"))
    )
    (net (code "52") (name "Net-(D6-A)") (class "Default")
      (node (ref "D6") (pin "1") (pinfunction "A_1") (pintype "passive"))
      (node (ref "R26") (pin "1") (pintype "passive"))
    )
    (net (code "53") (name "Net-(D7-A)") (class "Default")
      (node (ref "D7") (pin "1") (pinfunction "A_1") (pintype "passive"))
      (node (ref "R27") (pin "1") (pintype "passive"))
    )
    (net (code "54") (name "Net-(D8-A)") (class "Default")
      (node (ref "D8") (pin "1") (pinfunction "A_1") (pintype "passive"))
      (node (ref "R28") (pin "1") (pintype "passive"))
    )
    (net (code "55") (name "Net-(D9-A)") (class "Default")
      (node (ref "D9") (pin "1") (pinfunction "A_1") (pintype "passive"))
      (node (ref "R29") (pin "1") (pintype "passive"))
    )
    (net (code "56") (name "Net-(D10-A)") (class "Default")
      (node (ref "D10") (pin "1") (pinfunction "A_1") (pintype "passive"))
      (node (ref "R31") (pin "1") (pintype "passive"))
    )
    (net (code "57") (name "Net-(D11-A)") (class "Default")
      (node (ref "D11") (pin "1") (pinfunction "A_1") (pintype "passive"))
      (node (ref "L1") (pin "2") (pinfunction "2_2") (pintype "passive"))
      (node (ref "U3") (pin "1") (pinfunction "SW_1") (pintype "passive"))
    )
    (net (code "58") (name "Net-(P5-Pad2)") (class "Default")
      (node (ref "P5") (pin "2") (pinfunction "2_2") (pintype "passive"))
      (node (ref "R12") (pin "1") (pintype "passive"))
    )
    (net (code "59") (name "Net-(Q1-D)") (class "Default")
      (node (ref "P1") (pin "2") (pinfunction "2_2") (pintype "passive"))
      (node (ref "Q1") (pin "3") (pinfunction "D_3") (pintype "passive"))
    )
    (net (code "60") (name "Net-(Q2-D)") (class "Default")
      (node (ref "P2") (pin "2") (pinfunction "2_2") (pintype "passive"))
      (node (ref "Q2") (pin "3") (pinfunction "D_3") (pintype "passive"))
    )
    (net (code "61") (name "Net-(Q3-D)") (class "Default")
      (node (ref "P3") (pin "2") (pinfunction "2_2") (pintype "passive"))
      (node (ref "Q3") (pin "3") (pinfunction "D_3") (pintype "passive"))
    )
    (net (code "62") (name "Net-(Q4-D)") (class "Default")
      (node (ref "P4") (pin "2") (pinfunction "2_2") (pintype "passive"))
      (node (ref "Q4") (pin "3") (pinfunction "D_3") (pintype "passive"))
    )
    (net (code "63") (name "Net-(U2-CPOUT)") (class "Default")
      (node (ref "C16") (pin "2") (pinfunction "2_2") (pintype "passive"))
      (node (ref "U2") (pin "20") (pinfunction "CPOUT_20") (pintype "passive"))
    )
    (net (code "64") (name "Net-(U2-REGOUT)") (class "Default")
      (node (ref "C17") (pin "2") (pinfunction "2_2") (pintype "passive"))
      (node (ref "U2") (pin "10") (pinfunction "REGOUT_10") (pintype "passive"))
    )
    (net (code "65") (name "Net-(U3-EN)") (class "Default")
      (node (ref "R3") (pin "2") (pinfunction "2_2") (pintype "passive"))
      (node (ref "U3") (pin "4") (pinfunction "EN_4") (pintype "passive"))
    )
    (net (code "66") (name "Net-(U3-FB)") (class "Default")
      (node (ref "C3") (pin "1") (pinfunction "1_1") (pintype "passive"))
      (node (ref "R1") (pin "1") (pinfunction "1_1") (pintype "passive"))
      (node (ref "R2") (pin "2") (pinfunction "2_2") (pintype "passive"))
      (node (ref "U3") (pin "3") (pinfunction "FB_3") (pintype "passive"))
    )
    (net (code "67") (name "Net-(U4-OUT)") (class "Default")
      (node (ref "C6") (pin "2") (pinfunction "2_2") (pintype "passive"))
      (node (ref "C7") (pin "1") (pinfunction "1_1") (pintype "passive"))
      (node (ref "R18") (pin "1") (pintype "passive"))
      (node (ref "U4") (pin "3") (pinfunction "OUT_3") (pintype "passive"))
    )
    (net (code "68") (name "VBAT") (class "Default")
      (node (ref "C1") (pin "1") (pinfunction "1_1") (pintype "passive"))
      (node (ref "L1") (pin "1") (pinfunction "1_1") (pintype "passive"))
      (node (ref "P1") (pin "1") (pinfunction "1_1") (pintype "passive"))
      (node (ref "P2") (pin "1") (pinfunction "1_1") (pintype "passive"))
      (node (ref "P3") (pin "1") (pinfunction "1_1") (pintype "passive"))
      (node (ref "P4") (pin "1") (pinfunction "1_1") (pintype "passive"))
      (node (ref "R3") (pin "1") (pinfunction "1_1") (pintype "passive"))
      (node (ref "R4") (pin "2") (pinfunction "2_2") (pintype "passive"))
      (node (ref "S1") (pin "2") (pinfunction "COM1_2") (pintype "passive"))
      (node (ref "U3") (pin "5") (pinfunction "IN_5") (pintype "passive"))
    )
    (net (code "69") (name "VCC3V3") (class "Default")
      (node (ref "C14") (pin "2") (pinfunction "2_2") (pintype "passive"))
      (node (ref "C15") (pin "2") (pinfunction "2_2") (pintype "passive"))
      (node (ref "C18") (pin "2") (pintype "passive"))
      (node (ref "C19") (pin "2") (pintype "passive"))
      (node (ref "C98") (pin "1") (pintype "passive"))
      (node (ref "C99") (pin "1") (pintype "passive"))
      (node (ref "P5") (pin "3") (pinfunction "3_3") (pintype "passive"))
      (node (ref "P6") (pin "1") (pinfunction "1_1") (pintype "passive"))
      (node (ref "P7") (pin "1") (pinfunction "1_1") (pintype "passive"))
      (node (ref "P8") (pin "1") (pinfunction "1_1") (pintype "passive"))
      (node (ref "P9") (pin "1") (pinfunction "1_1") (pintype "passive"))
      (node (ref "R11") (pin "2") (pintype "passive"))
      (node (ref "R14") (pin "1") (pintype "passive"))
      (node (ref "R15") (pin "1") (pintype "passive"))
      (node (ref "R18") (pin "2") (pintype "passive"))
      (node (ref "R20") (pin "2") (pintype "passive"))
      (node (ref "R21") (pin "2") (pintype "passive"))
      (node (ref "R22") (pin "2") (pintype "passive"))
      (node (ref "R23") (pin "2") (pintype "passive"))
      (node (ref "R24") (pin "2") (pintype "passive"))
      (node (ref "R25") (pin "2") (pintype "passive"))
      (node (ref "R26") (pin "2") (pintype "passive"))
      (node (ref "R27") (pin "2") (pintype "passive"))
      (node (ref "R28") (pin "2") (pintype "passive"))
      (node (ref "R29") (pin "2") (pintype "passive"))
      (node (ref "U1") (pin "1") (pinfunction "VBAT_1") (pintype "power_in"))
      (node (ref "U1") (pin "24") (pinfunction "VDD_1_24") (pintype "power_in"))
      (node (ref "U1") (pin "36") (pinfunction "VDD_2_36") (pintype "power_in"))
      (node (ref "U1") (pin "48") (pinfunction "VDD_3_48") (pintype "power_in"))
      (node (ref "U1") (pin "9") (pinfunction "VDDA_9") (pintype "power_in"))
      (node (ref "U2") (pin "13") (pinfunction "VDD_13") (pintype "passive"))
      (node (ref "U2") (pin "8") (pinfunction "VLOGIC_8") (pintype "passive"))
      (node (ref "U5") (pin "12") (pinfunction "VDD3V3_12") (pintype "passive"))
      (node (ref "U6") (pin "2") (pinfunction "2_2") (pintype "passive"))
    )
    (net (code "70") (name "unconnected-(S1-CL1-Pad3)") (class "Default")
      (node (ref "S1") (pin "3") (pinfunction "CL1_3") (pintype "passive"))
    )
    (net (code "71") (name "unconnected-(S1-CL2-Pad4)") (class "Default")
      (node (ref "S1") (pin "4") (pinfunction "CL2_4") (pintype "passive"))
    )
    (net (code "72") (name "unconnected-(S1-COM2-Pad5)") (class "Default")
      (node (ref "S1") (pin "5") (pinfunction "COM2_5") (pintype "passive"))
    )
    (net (code "73") (name "unconnected-(S1-OP2-Pad6)") (class "Default")
      (node (ref "S1") (pin "6") (pinfunction "OP2_6") (pintype "passive"))
    )
    (net (code "74") (name "unconnected-(U2-AUX_CL-Pad7)") (class "Default")
      (node (ref "U2") (pin "7") (pinfunction "AUX_CL_7") (pintype "passive+no_connect"))
    )
    (net (code "75") (name "unconnected-(U2-AUX_DA-Pad6)") (class "Default")
      (node (ref "U2") (pin "6") (pinfunction "AUX_DA_6") (pintype "passive+no_connect"))
    )
    (net (code "76") (name "unconnected-(U2-NC-Pad2)") (class "Default")
      (node (ref "U2") (pin "2") (pinfunction "NC_2") (pintype "passive+no_connect"))
    )
    (net (code "77") (name "unconnected-(U2-NC-Pad3)") (class "Default")
      (node (ref "U2") (pin "3") (pinfunction "NC_3") (pintype "passive+no_connect"))
    )
    (net (code "78") (name "unconnected-(U2-NC-Pad4)") (class "Default")
      (node (ref "U2") (pin "4") (pinfunction "NC_4") (pintype "passive+no_connect"))
    )
    (net (code "79") (name "unconnected-(U2-NC-Pad5)") (class "Default")
      (node (ref "U2") (pin "5") (pinfunction "NC_5") (pintype "passive+no_connect"))
    )
    (net (code "80") (name "unconnected-(U2-NC-Pad14)") (class "Default")
      (node (ref "U2") (pin "14") (pinfunction "NC_14") (pintype "passive+no_connect"))
    )
    (net (code "81") (name "unconnected-(U2-NC-Pad15)") (class "Default")
      (node (ref "U2") (pin "15") (pinfunction "NC_15") (pintype "passive+no_connect"))
    )
    (net (code "82") (name "unconnected-(U2-NC-Pad16)") (class "Default")
      (node (ref "U2") (pin "16") (pinfunction "NC_16") (pintype "passive+no_connect"))
    )
    (net (code "83") (name "unconnected-(U2-NC-Pad17)") (class "Default")
      (node (ref "U2") (pin "17") (pinfunction "NC_17") (pintype "passive+no_connect"))
    )
    (net (code "84") (name "unconnected-(U2-RESV-Pad19)") (class "Default")
      (node (ref "U2") (pin "19") (pinfunction "RESV_19") (pintype "passive+no_connect"))
    )
    (net (code "85") (name "unconnected-(U2-RESV-Pad21)") (class "Default")
      (node (ref "U2") (pin "21") (pinfunction "RESV_21") (pintype "passive+no_connect"))
    )
    (net (code "86") (name "unconnected-(U2-RESV-Pad22)") (class "Default")
      (node (ref "U2") (pin "22") (pinfunction "RESV_22") (pintype "passive+no_connect"))
    )
    (net (code "87") (name "unconnected-(U3-NC-Pad6)") (class "Default")
      (node (ref "U3") (pin "6") (pinfunction "NC_6") (pintype "passive+no_connect"))
    )
    (net (code "88") (name "unconnected-(U5-GND-Pad14)") (class "Default")
      (node (ref "U5") (pin "14") (pinfunction "GND_14") (pintype "passive"))
    )
    (net (code "89") (name "unconnected-(U5-NC-Pad3)") (class "Default")
      (node (ref "U5") (pin "3") (pinfunction "NC_3") (pintype "passive"))
    )
    (net (code "90") (name "unconnected-(U5-NC-Pad4)") (class "Default")
      (node (ref "U5") (pin "4") (pinfunction "NC_4") (pintype "passive"))
    )
    (net (code "91") (name "unconnected-(U5-NC-Pad10)") (class "Default")
      (node (ref "U5") (pin "10") (pinfunction "NC_10") (pintype "passive"))
    )
    (net (code "92") (name "unconnected-(U5-NC-Pad18)") (class "Default")
      (node (ref "U5") (pin "18") (pinfunction "NC_18") (pintype "passive"))
    )
    (net (code "93") (name "unconnected-(U5-NC-Pad19)") (class "Default")
      (node (ref "U5") (pin "19") (pinfunction "NC_19") (pintype "passive"))
    )
    (net (code "94") (name "unconnected-(U5-NC-Pad23)") (class "Default")
      (node (ref "U5") (pin "23") (pinfunction "NC_23") (pintype "passive"))
    )
    (net (code "95") (name "unconnected-(U5-NC-Pad31)") (class "Default")
      (node (ref "U5") (pin "31") (pinfunction "NC_31") (pintype "passive"))
    )
    (net (code "96") (name "unconnected-(U5-NC-Pad32)") (class "Default")
      (node (ref "U5") (pin "32") (pinfunction "NC_32") (pintype "passive"))
    )
    (net (code "97") (name "unconnected-(U5-P00-Pad5)") (class "Default")
      (node (ref "U5") (pin "5") (pinfunction "P00_5") (pintype "passive"))
    )
    (net (code "98") (name "unconnected-(U5-P01-Pad6)") (class "Default")
      (node (ref "U5") (pin "6") (pinfunction "P01_6") (pintype "passive"))
    )
    (net (code "99") (name "unconnected-(U5-P04-Pad33)") (class "Default")
      (node (ref "U5") (pin "33") (pinfunction "P04_33") (pintype "passive"))
    )
    (net (code "100") (name "unconnected-(U5-P05-Pad25)") (class "Default")
      (node (ref "U5") (pin "25") (pinfunction "P05_25") (pintype "passive"))
    )
    (net (code "101") (name "unconnected-(U5-P06-Pad26)") (class "Default")
      (node (ref "U5") (pin "26") (pinfunction "P06_26") (pintype "passive"))
    )
    (net (code "102") (name "unconnected-(U5-P07-Pad27)") (class "Default")
      (node (ref "U5") (pin "27") (pinfunction "P07_27") (pintype "passive"))
    )
    (net (code "103") (name "unconnected-(U5-P10-Pad15)") (class "Default")
      (node (ref "U5") (pin "15") (pinfunction "P10_15") (pintype "passive"))
    )
    (net (code "104") (name "unconnected-(U5-P11-Pad34)") (class "Default")
      (node (ref "U5") (pin "34") (pinfunction "P11_34") (pintype "passive"))
    )
    (net (code "105") (name "unconnected-(U5-P14-Pad16)") (class "Default")
      (node (ref "U5") (pin "16") (pinfunction "P14_16") (pintype "passive"))
    )
    (net (code "106") (name "unconnected-(U5-P23-Pad28)") (class "Default")
      (node (ref "U5") (pin "28") (pinfunction "P23_28") (pintype "passive"))
    )
    (net (code "107") (name "unconnected-(U5-P24-Pad29)") (class "Default")
      (node (ref "U5") (pin "29") (pinfunction "P24_29") (pintype "passive"))
    )
    (net (code "108") (name "unconnected-(U5-P26-Pad30)") (class "Default")
      (node (ref "U5") (pin "30") (pinfunction "P26_30") (pintype "passive"))
    )
    (net (code "109") (name "unconnected-(U5-P35-Pad8)") (class "Default")
      (node (ref "U5") (pin "8") (pinfunction "P35_8") (pintype "passive"))
    )
    (net (code "110") (name "unconnected-(U5-P36-Pad17)") (class "Default")
      (node (ref "U5") (pin "17") (pinfunction "P36_17") (pintype "passive"))
    )
    (net (code "111") (name "unconnected-(U5-P40-Pad7)") (class "Default")
      (node (ref "U5") (pin "7") (pinfunction "P40_7") (pintype "passive"))
    )
    (net (code "112") (name "unconnected-(U5-P45-Pad9)") (class "Default")
      (node (ref "U5") (pin "9") (pinfunction "P45_9") (pintype "passive"))
    )
    (net (code "113") (name "unconnected-(U5-PRSTN-Pad11)") (class "Default")
      (node (ref "U5") (pin "11") (pinfunction "PRSTN_11") (pintype "passive"))
    )
    (net (code "114") (name "unconnected-(U5-RST-Pad20)") (class "Default")
      (node (ref "U5") (pin "20") (pinfunction "RST_20") (pintype "passive"))
    )
  )
)
